# A9G_AHRS.net
KiCad netlist of a schematic drawn in Altium Designer
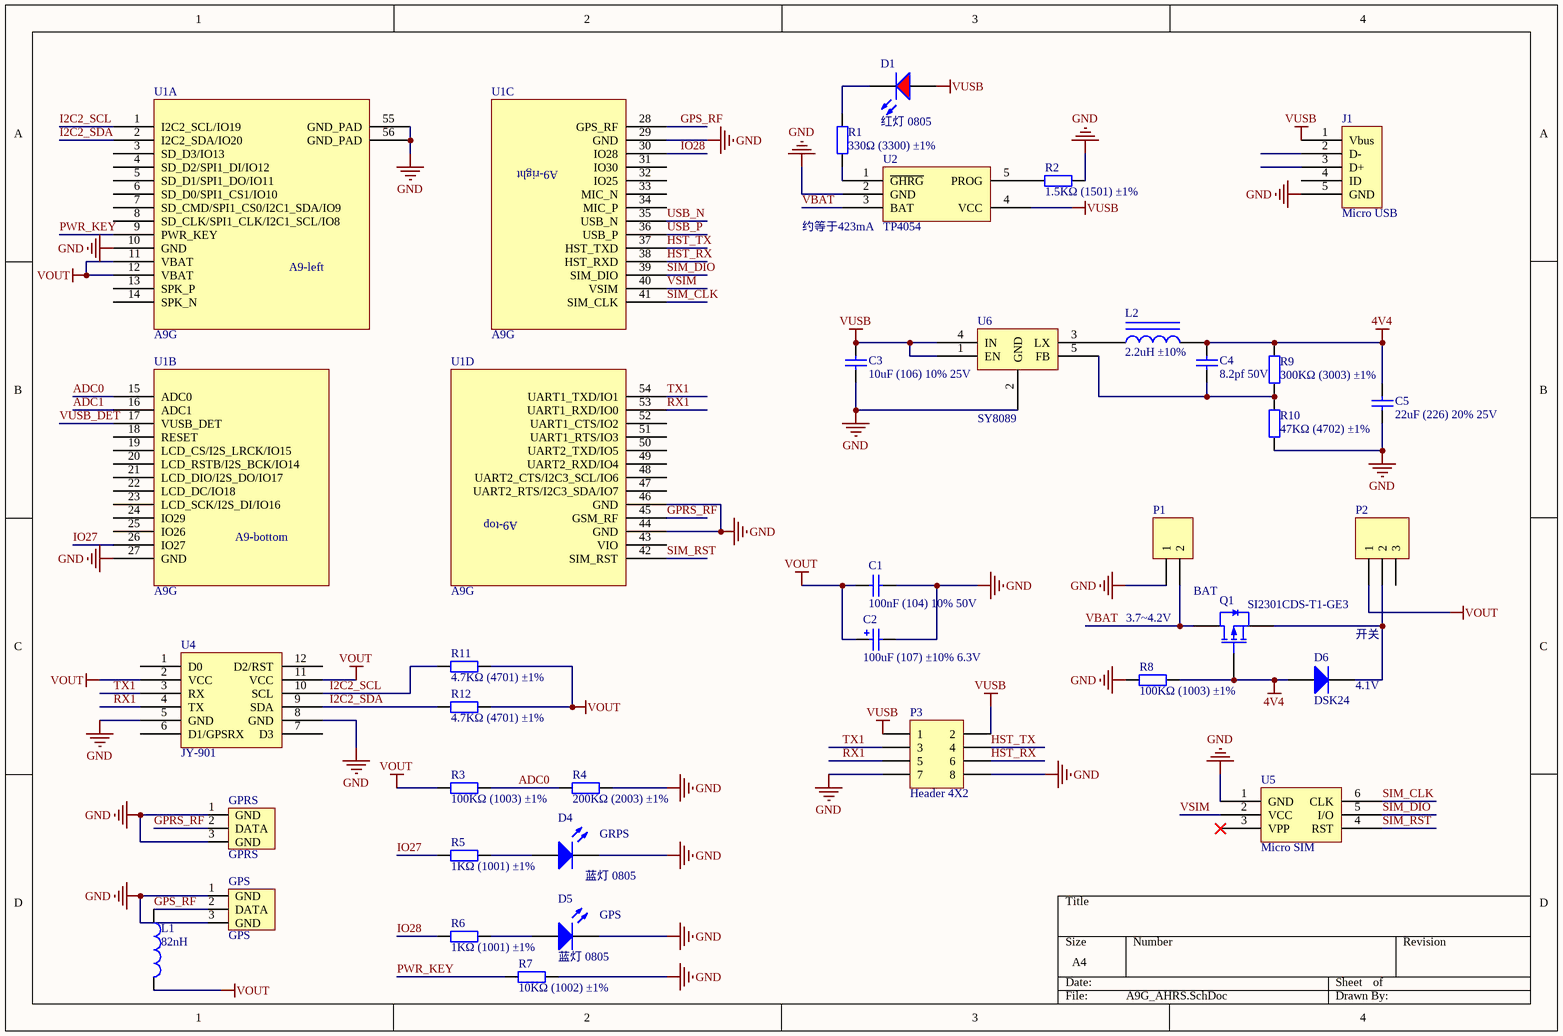
[diagram p0: A9G_AHRS.SchDoc]

(export (version "E")
  (design (tool "Eeschema 10.0.6"))
  (components
    (comp (ref "C1")
      (value "100nF (104) 10% 50V")
      (footprint "LC-0603_C")
      (description "贴片电容")
      (libsource (lib "Miscellaneous Devices LC") (part "0603 100nF (104) 10% 50V"))
    )
    (comp (ref "C2")
      (value "100uF (107) ±10% 6.3V")
      (footprint "LC-CASE-B_3528")
      (description "钽电容")
      (libsource (lib "Miscellaneous Devices LC") (part "3528 100uF (107) 10% 6.3V"))
    )
    (comp (ref "C3")
      (value "10uF (106) 10% 25V")
      (footprint "LC-0805_C")
      (description "贴片电容")
      (libsource (lib "Miscellaneous Devices LC") (part "0805 10uF (106) 10% 25V"))
    )
    (comp (ref "C4")
      (value "8.2pf 50V")
      (footprint "LC-0805_C")
      (description "贴片电容")
      (libsource (lib "Miscellaneous Devices LC") (part "0805 100nF(104) 10% 50V"))
    )
    (comp (ref "C5")
      (value "22uF (226) 20% 25V")
      (footprint "LC-0805_C")
      (description "贴片电容")
      (libsource (lib "Miscellaneous Devices LC") (part "0805 22uF (226) 20% 25V"))
    )
    (comp (ref "D1")
      (value "红灯 0805")
      (footprint "LC-0805_LED_S1")
      (description "发光二极管")
      (libsource (lib "Miscellaneous Devices LC") (part "0805 红灯"))
    )
    (comp (ref "D4")
      (value "蓝灯 0805")
      (footprint "LC-0805_LED_S1")
      (description "发光二极管")
      (libsource (lib "Miscellaneous Devices LC") (part "0805 蓝灯"))
    )
    (comp (ref "D5")
      (value "蓝灯 0805")
      (footprint "LC-0805_LED_S1")
      (description "发光二极管")
      (libsource (lib "Miscellaneous Devices LC") (part "0805 蓝灯"))
    )
    (comp (ref "D6")
      (value "DSK24")
      (footprint "LC-SOD-123")
      (description "肖特基二极管")
      (libsource (lib "Miscellaneous Devices LC") (part "SOD-123 B5819W  SL"))
    )
    (comp (ref "GPRS")
      (value "GPRS")
      (footprint "IPEX")
      (description "IPEX座")
      (libsource (lib "ATK_S1216F8_BD_V1.1") (part "IPEX"))
    )
    (comp (ref "GPS")
      (value "GPS")
      (footprint "IPEX")
      (description "IPEX座")
      (libsource (lib "ATK_S1216F8_BD_V1.1") (part "IPEX"))
    )
    (comp (ref "J1")
      (value "Micro USB")
      (footprint "Micro USB")
      (description "micro usb 母座")
      (libsource (lib "MyLib") (part "Micro USB"))
    )
    (comp (ref "L1")
      (value "82nH")
      (footprint "LC-0805_L")
      (description "Inductor")
      (fields (field (name "PUBLISHER") "Altium Limited"))
      (libsource (lib "Miscellaneous Devices") (part "Inductor"))
    )
    (comp (ref "L2")
      (value "2.2uH ±10%")
      (footprint "3015")
      (description "贴片电感")
      (libsource (lib "Miscellaneous Devices LC") (part "0805 2.2uH 10%"))
    )
    (comp (ref "P1")
      (value "BAT")
      (footprint "Motor_Header")
      (description "Header, 2-Pin")
      (fields (field (name "PUBLISHER") "Altium Limited"))
      (libsource (lib "Miscellaneous Connectors") (part "Header 2"))
    )
    (comp (ref "P2")
      (value "开关")
      (footprint "SW_6726")
      (description "Header, 3-Pin, Right Angle")
      (fields (field (name "PUBLISHER") "Altium Limited"))
      (libsource (lib "Miscellaneous Connectors") (part "Header 3H"))
    )
    (comp (ref "P3")
      (value "Header 4X2")
      (footprint "HDR2X4")
      (description "Header, 4-Pin, Dual row")
      (fields (field (name "PUBLISHER") "Altium Limited"))
      (libsource (lib "Miscellaneous Connectors") (part "Header 4X2"))
    )
    (comp (ref "Q1")
      (value "SI2301CDS-T1-GE3")
      (footprint "LC-SOT-23(SOT-23-3)")
      (description "MOS(场效应管)")
      (libsource (lib "Miscellaneous Devices LC") (part "SI2301CDS-T1-GE3"))
    )
    (comp (ref "R1")
      (value "330Ω (3300) ±1%")
      (footprint "LC-0805_R")
      (description "贴片电阻")
      (libsource (lib "Miscellaneous Devices LC") (part "0805 330Ω (3300) 1%"))
    )
    (comp (ref "R2")
      (value "1.5KΩ (1501) ±1%")
      (footprint "LC-0805_R")
      (description "贴片电阻")
      (libsource (lib "Miscellaneous Devices LC") (part "0805 1.5KΩ (1501) 1%"))
    )
    (comp (ref "R3")
      (value "100KΩ (1003) ±1%")
      (footprint "LC-0805_R")
      (description "贴片电阻")
      (libsource (lib "Miscellaneous Devices LC") (part "0805 100KΩ (1003) 1%"))
    )
    (comp (ref "R4")
      (value "200KΩ (2003) ±1%")
      (footprint "LC-0805_R")
      (description "贴片电阻")
      (libsource (lib "Miscellaneous Devices LC") (part "0805 200KΩ (2003) 1%"))
    )
    (comp (ref "R5")
      (value "1KΩ (1001) ±1%")
      (footprint "LC-0805_R")
      (description "贴片电阻")
      (libsource (lib "Miscellaneous Devices LC") (part "0805 1KΩ (1001) 1%"))
    )
    (comp (ref "R6")
      (value "1KΩ (1001) ±1%")
      (footprint "LC-0805_R")
      (description "贴片电阻")
      (libsource (lib "Miscellaneous Devices LC") (part "0805 1KΩ (1001) 1%"))
    )
    (comp (ref "R7")
      (value "10KΩ (1002) ±1%")
      (footprint "LC-0805_R")
      (description "贴片电阻")
      (libsource (lib "Miscellaneous Devices LC") (part "0805 10KΩ (1002) 1%"))
    )
    (comp (ref "R8")
      (value "100KΩ (1003) ±1%")
      (footprint "LC-0805_R")
      (description "贴片电阻")
      (libsource (lib "Miscellaneous Devices LC") (part "0805 100KΩ (1003) 1%"))
    )
    (comp (ref "R9")
      (value "300KΩ (3003) ±1%")
      (footprint "LC-0805_R")
      (description "贴片电阻")
      (libsource (lib "Miscellaneous Devices LC") (part "0805 300KΩ (3003) 1%"))
    )
    (comp (ref "R10")
      (value "47KΩ (4702) ±1%")
      (footprint "LC-0805_R")
      (description "贴片电阻")
      (libsource (lib "Miscellaneous Devices LC") (part "0805 47KΩ (4702) 1%"))
    )
    (comp (ref "R11")
      (value "4.7KΩ (4701) ±1%")
      (footprint "LC-0805_R")
      (description "贴片电阻")
      (libsource (lib "Miscellaneous Devices LC") (part "0805 4.7KΩ (4701) 1%"))
    )
    (comp (ref "R12")
      (value "4.7KΩ (4701) ±1%")
      (footprint "LC-0805_R")
      (description "贴片电阻")
      (libsource (lib "Miscellaneous Devices LC") (part "0805 4.7KΩ (4701) 1%"))
    )
    (comp (ref "U1") (value "A9G") (footprint "A9") (libsource (lib "") (part "A9_1")))
    (comp (ref "U2")
      (value "TP4054")
      (footprint "LC-SOT-23-5")
      (description "电池电源管理")
      (libsource (lib "Miscellaneous Devices LC") (part "TP4054"))
    )
    (comp (ref "U4")
      (value "JY-901")
      (footprint "JY-901")
      (description "君悦智控高精度9轴传感器")
      (libsource (lib "JYModule") (part "JY-901"))
    )
    (comp (ref "U5") (value "Micro SIM") (footprint "Micro SIM") (libsource (lib "MyLib") (part "Micro SIM")))
    (comp (ref "U6")
      (value "SY8089")
      (footprint "LC-SOT-23-5")
      (description "DC-DC regulator IC  capable of delivering up to 2A output current.")
      (libsource (lib "MyLib") (part "SY8089"))
    )
  )
  (nets
    (net (code "1") (name "/ADC0") (class "Default")
      (node (ref "R3") (pin "2") (pinfunction "2_2") (pintype "passive"))
      (node (ref "R4") (pin "1") (pinfunction "1_1") (pintype "passive"))
      (node (ref "U1") (pin "15") (pinfunction "ADC0_15") (pintype "passive"))
    )
    (net (code "2") (name "/ADC1") (class "Default")
      (node (ref "U1") (pin "16") (pinfunction "ADC1_16") (pintype "passive"))
    )
    (net (code "3") (name "/GPRS_RF") (class "Default")
      (node (ref "GPRS") (pin "2") (pinfunction "DATA_2") (pintype "passive"))
      (node (ref "U1") (pin "45") (pinfunction "GSM_RF_45") (pintype "passive"))
    )
    (net (code "4") (name "/GPS_RF") (class "Default")
      (node (ref "GPS") (pin "2") (pinfunction "DATA_2") (pintype "passive"))
      (node (ref "L1") (pin "1") (pinfunction "1_1") (pintype "passive"))
      (node (ref "U1") (pin "28") (pinfunction "GPS_RF_28") (pintype "passive"))
    )
    (net (code "5") (name "/HST_RX") (class "Default")
      (node (ref "P3") (pin "6") (pinfunction "6_6") (pintype "passive"))
      (node (ref "U1") (pin "38") (pinfunction "HST_RXD_38") (pintype "passive"))
    )
    (net (code "6") (name "/HST_TX") (class "Default")
      (node (ref "P3") (pin "4") (pinfunction "4_4") (pintype "passive"))
      (node (ref "U1") (pin "37") (pinfunction "HST_TXD_37") (pintype "passive"))
    )
    (net (code "7") (name "/I2C2_SCL") (class "Default")
      (node (ref "R11") (pin "1") (pinfunction "1_1") (pintype "passive"))
      (node (ref "U1") (pin "1") (pinfunction "I2C2_SCL/IO19_1") (pintype "passive"))
      (node (ref "U4") (pin "10") (pinfunction "SCL_10") (pintype "passive"))
    )
    (net (code "8") (name "/I2C2_SDA") (class "Default")
      (node (ref "R12") (pin "1") (pinfunction "1_1") (pintype "passive"))
      (node (ref "U1") (pin "2") (pinfunction "I2C2_SDA/IO20_2") (pintype "passive"))
      (node (ref "U4") (pin "9") (pinfunction "SDA_9") (pintype "passive"))
    )
    (net (code "9") (name "/IO27") (class "Default")
      (node (ref "R5") (pin "1") (pinfunction "1_1") (pintype "passive"))
      (node (ref "U1") (pin "26") (pinfunction "IO27_26") (pintype "passive"))
    )
    (net (code "10") (name "/IO28") (class "Default")
      (node (ref "R6") (pin "1") (pinfunction "1_1") (pintype "passive"))
      (node (ref "U1") (pin "30") (pinfunction "IO28_30") (pintype "passive"))
    )
    (net (code "11") (name "/PWR_KEY") (class "Default")
      (node (ref "R7") (pin "1") (pinfunction "1_1") (pintype "passive"))
      (node (ref "U1") (pin "9") (pinfunction "PWR_KEY_9") (pintype "passive"))
    )
    (net (code "12") (name "/RX1") (class "Default")
      (node (ref "P3") (pin "5") (pinfunction "5_5") (pintype "passive"))
      (node (ref "U1") (pin "53") (pinfunction "UART1_RXD/IO0_53") (pintype "passive"))
      (node (ref "U4") (pin "4") (pinfunction "TX_4") (pintype "passive"))
    )
    (net (code "13") (name "/SIM_CLK") (class "Default")
      (node (ref "U1") (pin "41") (pinfunction "SIM_CLK_41") (pintype "passive"))
      (node (ref "U5") (pin "6") (pinfunction "CLK_6") (pintype "passive"))
    )
    (net (code "14") (name "/SIM_DIO") (class "Default")
      (node (ref "U1") (pin "39") (pinfunction "SIM_DIO_39") (pintype "passive"))
      (node (ref "U5") (pin "5") (pinfunction "I/O_5") (pintype "passive"))
    )
    (net (code "15") (name "/SIM_RST") (class "Default")
      (node (ref "U1") (pin "42") (pinfunction "SIM_RST_42") (pintype "passive"))
      (node (ref "U5") (pin "4") (pinfunction "RST_4") (pintype "passive"))
    )
    (net (code "16") (name "/TX1") (class "Default")
      (node (ref "P3") (pin "3") (pinfunction "3_3") (pintype "passive"))
      (node (ref "U1") (pin "54") (pinfunction "UART1_TXD/IO1_54") (pintype "passive"))
      (node (ref "U4") (pin "3") (pinfunction "RX_3") (pintype "passive"))
    )
    (net (code "17") (name "/USB_N") (class "Default")
      (node (ref "U1") (pin "35") (pinfunction "USB_N_35") (pintype "passive"))
    )
    (net (code "18") (name "/USB_P") (class "Default")
      (node (ref "U1") (pin "36") (pinfunction "USB_P_36") (pintype "passive"))
    )
    (net (code "19") (name "/VBAT") (class "Default")
      (node (ref "P1") (pin "2") (pinfunction "2_2") (pintype "passive"))
      (node (ref "Q1") (pin "3") (pinfunction "D_3") (pintype "passive"))
      (node (ref "U2") (pin "3") (pinfunction "BAT_3") (pintype "passive"))
    )
    (net (code "20") (name "/VSIM") (class "Default")
      (node (ref "U1") (pin "40") (pinfunction "VSIM_40") (pintype "passive"))
      (node (ref "U5") (pin "2") (pinfunction "VCC_2") (pintype "passive"))
    )
    (net (code "21") (name "/VUSB_DET") (class "Default")
      (node (ref "U1") (pin "17") (pinfunction "VUSB_DET_17") (pintype "passive"))
    )
    (net (code "22") (name "4V4") (class "Default")
      (node (ref "C4") (pin "2") (pinfunction "2_2") (pintype "passive"))
      (node (ref "C5") (pin "2") (pinfunction "2_2") (pintype "passive"))
      (node (ref "D6") (pin "1") (pinfunction "A_1") (pintype "passive"))
      (node (ref "L2") (pin "2") (pinfunction "2_2") (pintype "passive"))
      (node (ref "Q1") (pin "1") (pinfunction "G_1") (pintype "passive"))
      (node (ref "R8") (pin "2") (pinfunction "2_2") (pintype "passive"))
      (node (ref "R9") (pin "2") (pinfunction "2_2") (pintype "passive"))
    )
    (net (code "23") (name "GND") (class "Default")
      (node (ref "C1") (pin "2") (pinfunction "2_2") (pintype "passive"))
      (node (ref "C2") (pin "2") (pinfunction "2_2") (pintype "passive"))
      (node (ref "C3") (pin "1") (pinfunction "1_1") (pintype "passive"))
      (node (ref "C5") (pin "1") (pinfunction "1_1") (pintype "passive"))
      (node (ref "D4") (pin "K") (pinfunction "K_K") (pintype "passive"))
      (node (ref "D5") (pin "K") (pinfunction "K_K") (pintype "passive"))
      (node (ref "GPRS") (pin "1") (pinfunction "GND_1") (pintype "passive"))
      (node (ref "GPRS") (pin "3") (pinfunction "GND_3") (pintype "passive"))
      (node (ref "GPS") (pin "1") (pinfunction "GND_1") (pintype "passive"))
      (node (ref "GPS") (pin "3") (pinfunction "GND_3") (pintype "passive"))
      (node (ref "J1") (pin "5") (pinfunction "GND_5") (pintype "passive"))
      (node (ref "P1") (pin "1") (pinfunction "1_1") (pintype "passive"))
      (node (ref "P3") (pin "7") (pinfunction "7_7") (pintype "passive"))
      (node (ref "P3") (pin "8") (pinfunction "8_8") (pintype "passive"))
      (node (ref "R10") (pin "1") (pinfunction "1_1") (pintype "passive"))
      (node (ref "R2") (pin "2") (pinfunction "2_2") (pintype "passive"))
      (node (ref "R4") (pin "2") (pinfunction "2_2") (pintype "passive"))
      (node (ref "R7") (pin "2") (pinfunction "2_2") (pintype "passive"))
      (node (ref "R8") (pin "1") (pinfunction "1_1") (pintype "passive"))
      (node (ref "U1") (pin "10") (pinfunction "GND_10") (pintype "passive"))
      (node (ref "U1") (pin "27") (pinfunction "GND_27") (pintype "passive"))
      (node (ref "U1") (pin "29") (pinfunction "GND_29") (pintype "passive"))
      (node (ref "U1") (pin "44") (pinfunction "GND_44") (pintype "passive"))
      (node (ref "U1") (pin "46") (pinfunction "GND_46") (pintype "passive"))
      (node (ref "U1") (pin "55") (pinfunction "GND_PAD_55") (pintype "passive"))
      (node (ref "U1") (pin "56") (pinfunction "GND_PAD_56") (pintype "passive"))
      (node (ref "U2") (pin "2") (pinfunction "GND_2") (pintype "passive"))
      (node (ref "U4") (pin "5") (pinfunction "GND_5") (pintype "passive"))
      (node (ref "U4") (pin "8") (pinfunction "GND_8") (pintype "passive"))
      (node (ref "U5") (pin "1") (pinfunction "GND_1") (pintype "passive"))
      (node (ref "U6") (pin "2") (pinfunction "GND_2") (pintype "passive"))
    )
    (net (code "24") (name "Net-(D1-PadK)") (class "Default")
      (node (ref "D1") (pin "K") (pinfunction "K_K") (pintype "passive"))
      (node (ref "R1") (pin "2") (pinfunction "2_2") (pintype "passive"))
    )
    (net (code "25") (name "Net-(D4-PadA)") (class "Default")
      (node (ref "D4") (pin "A") (pinfunction "A_A") (pintype "passive"))
      (node (ref "R5") (pin "2") (pinfunction "2_2") (pintype "passive"))
    )
    (net (code "26") (name "Net-(D5-PadA)") (class "Default")
      (node (ref "D5") (pin "A") (pinfunction "A_A") (pintype "passive"))
      (node (ref "R6") (pin "2") (pinfunction "2_2") (pintype "passive"))
    )
    (net (code "27") (name "Net-(D6-K)") (class "Default")
      (node (ref "D6") (pin "2") (pinfunction "K_2") (pintype "passive"))
      (node (ref "P2") (pin "2") (pinfunction "2_2") (pintype "passive"))
      (node (ref "Q1") (pin "2") (pinfunction "S_2") (pintype "passive"))
    )
    (net (code "28") (name "Net-(U2-PROG)") (class "Default")
      (node (ref "R2") (pin "1") (pinfunction "1_1") (pintype "passive"))
      (node (ref "U2") (pin "5") (pinfunction "PROG_5") (pintype "passive"))
    )
    (net (code "29") (name "Net-(U2-~{GHRG})") (class "Default")
      (node (ref "R1") (pin "1") (pinfunction "1_1") (pintype "passive"))
      (node (ref "U2") (pin "1") (pinfunction "~{GHRG}_1") (pintype "passive"))
    )
    (net (code "30") (name "Net-(U6-FB)") (class "Default")
      (node (ref "C4") (pin "1") (pinfunction "1_1") (pintype "passive"))
      (node (ref "R10") (pin "2") (pinfunction "2_2") (pintype "passive"))
      (node (ref "R9") (pin "1") (pinfunction "1_1") (pintype "passive"))
      (node (ref "U6") (pin "5") (pinfunction "FB_5") (pintype "passive"))
    )
    (net (code "31") (name "Net-(U6-LX)") (class "Default")
      (node (ref "L2") (pin "1") (pinfunction "1_1") (pintype "passive"))
      (node (ref "U6") (pin "3") (pinfunction "LX_3") (pintype "passive"))
    )
    (net (code "32") (name "VOUT") (class "Default")
      (node (ref "C1") (pin "1") (pinfunction "1_1") (pintype "passive"))
      (node (ref "C2") (pin "1") (pinfunction "1_1") (pintype "passive"))
      (node (ref "L1") (pin "2") (pinfunction "2_2") (pintype "passive"))
      (node (ref "P2") (pin "1") (pinfunction "1_1") (pintype "passive"))
      (node (ref "R11") (pin "2") (pinfunction "2_2") (pintype "passive"))
      (node (ref "R12") (pin "2") (pinfunction "2_2") (pintype "passive"))
      (node (ref "R3") (pin "1") (pinfunction "1_1") (pintype "passive"))
      (node (ref "U1") (pin "11") (pinfunction "VBAT_11") (pintype "passive"))
      (node (ref "U1") (pin "12") (pinfunction "VBAT_12") (pintype "passive"))
      (node (ref "U4") (pin "11") (pinfunction "VCC_11") (pintype "passive"))
      (node (ref "U4") (pin "2") (pinfunction "VCC_2") (pintype "passive"))
    )
    (net (code "33") (name "VUSB") (class "Default")
      (node (ref "C3") (pin "2") (pinfunction "2_2") (pintype "passive"))
      (node (ref "D1") (pin "A") (pinfunction "A_A") (pintype "passive"))
      (node (ref "J1") (pin "1") (pinfunction "Vbus_1") (pintype "passive"))
      (node (ref "P3") (pin "1") (pinfunction "1_1") (pintype "passive"))
      (node (ref "P3") (pin "2") (pinfunction "2_2") (pintype "passive"))
      (node (ref "U2") (pin "4") (pinfunction "VCC_4") (pintype "passive"))
      (node (ref "U6") (pin "1") (pinfunction "EN_1") (pintype "passive"))
      (node (ref "U6") (pin "4") (pinfunction "IN_4") (pintype "passive"))
    )
    (net (code "34") (name "unconnected-(J1-D+-Pad3)") (class "Default")
      (node (ref "J1") (pin "3") (pinfunction "D+_3") (pintype "passive"))
    )
    (net (code "35") (name "unconnected-(J1-D--Pad2)") (class "Default")
      (node (ref "J1") (pin "2") (pinfunction "D-_2") (pintype "passive"))
    )
    (net (code "36") (name "unconnected-(J1-ID-Pad4)") (class "Default")
      (node (ref "J1") (pin "4") (pinfunction "ID_4") (pintype "passive"))
    )
    (net (code "37") (name "unconnected-(P2-Pad3)") (class "Default")
      (node (ref "P2") (pin "3") (pinfunction "3_3") (pintype "passive"))
    )
    (net (code "38") (name "unconnected-(U1A-SD_CLK{slash}SPI1_CLK{slash}I2C1_SCL{slash}IO8-Pad8)") (class "Default")
      (node (ref "U1") (pin "8") (pinfunction "SD_CLK/SPI1_CLK/I2C1_SCL/IO8_8") (pintype "passive"))
    )
    (net (code "39") (name "unconnected-(U1A-SD_CMD{slash}SPI1_CS0{slash}I2C1_SDA{slash}IO9-Pad7)") (class "Default")
      (node (ref "U1") (pin "7") (pinfunction "SD_CMD/SPI1_CS0/I2C1_SDA/IO9_7") (pintype "passive"))
    )
    (net (code "40") (name "unconnected-(U1A-SD_D0{slash}SPI1_CS1{slash}IO10-Pad6)") (class "Default")
      (node (ref "U1") (pin "6") (pinfunction "SD_D0/SPI1_CS1/IO10_6") (pintype "passive"))
    )
    (net (code "41") (name "unconnected-(U1A-SD_D1{slash}SPI1_DO{slash}IO11-Pad5)") (class "Default")
      (node (ref "U1") (pin "5") (pinfunction "SD_D1/SPI1_DO/IO11_5") (pintype "passive"))
    )
    (net (code "42") (name "unconnected-(U1A-SD_D2{slash}SPI1_DI{slash}IO12-Pad4)") (class "Default")
      (node (ref "U1") (pin "4") (pinfunction "SD_D2/SPI1_DI/IO12_4") (pintype "passive"))
    )
    (net (code "43") (name "unconnected-(U1A-SD_D3{slash}IO13-Pad3)") (class "Default")
      (node (ref "U1") (pin "3") (pinfunction "SD_D3/IO13_3") (pintype "passive"))
    )
    (net (code "44") (name "unconnected-(U1A-SPK_N-Pad14)") (class "Default")
      (node (ref "U1") (pin "14") (pinfunction "SPK_N_14") (pintype "passive"))
    )
    (net (code "45") (name "unconnected-(U1A-SPK_P-Pad13)") (class "Default")
      (node (ref "U1") (pin "13") (pinfunction "SPK_P_13") (pintype "passive"))
    )
    (net (code "46") (name "unconnected-(U1B-IO26-Pad25)") (class "Default")
      (node (ref "U1") (pin "25") (pinfunction "IO26_25") (pintype "passive"))
    )
    (net (code "47") (name "unconnected-(U1B-IO29-Pad24)") (class "Default")
      (node (ref "U1") (pin "24") (pinfunction "IO29_24") (pintype "passive"))
    )
    (net (code "48") (name "unconnected-(U1B-LCD_CS{slash}I2S_LRCK{slash}IO15-Pad19)") (class "Default")
      (node (ref "U1") (pin "19") (pinfunction "LCD_CS/I2S_LRCK/IO15_19") (pintype "passive"))
    )
    (net (code "49") (name "unconnected-(U1B-LCD_DC{slash}IO18-Pad22)") (class "Default")
      (node (ref "U1") (pin "22") (pinfunction "LCD_DC/IO18_22") (pintype "passive"))
    )
    (net (code "50") (name "unconnected-(U1B-LCD_DIO{slash}I2S_DO{slash}IO17-Pad21)") (class "Default")
      (node (ref "U1") (pin "21") (pinfunction "LCD_DIO/I2S_DO/IO17_21") (pintype "passive"))
    )
    (net (code "51") (name "unconnected-(U1B-LCD_RSTB{slash}I2S_BCK{slash}IO14-Pad20)") (class "Default")
      (node (ref "U1") (pin "20") (pinfunction "LCD_RSTB/I2S_BCK/IO14_20") (pintype "passive"))
    )
    (net (code "52") (name "unconnected-(U1B-LCD_SCK{slash}I2S_DI{slash}IO16-Pad23)") (class "Default")
      (node (ref "U1") (pin "23") (pinfunction "LCD_SCK/I2S_DI/IO16_23") (pintype "passive"))
    )
    (net (code "53") (name "unconnected-(U1B-RESET-Pad18)") (class "Default")
      (node (ref "U1") (pin "18") (pinfunction "RESET_18") (pintype "passive"))
    )
    (net (code "54") (name "unconnected-(U1C-IO25-Pad32)") (class "Default")
      (node (ref "U1") (pin "32") (pinfunction "IO25_32") (pintype "passive"))
    )
    (net (code "55") (name "unconnected-(U1C-IO30-Pad31)") (class "Default")
      (node (ref "U1") (pin "31") (pinfunction "IO30_31") (pintype "passive"))
    )
    (net (code "56") (name "unconnected-(U1C-MIC_N-Pad33)") (class "Default")
      (node (ref "U1") (pin "33") (pinfunction "MIC_N_33") (pintype "passive"))
    )
    (net (code "57") (name "unconnected-(U1C-MIC_P-Pad34)") (class "Default")
      (node (ref "U1") (pin "34") (pinfunction "MIC_P_34") (pintype "passive"))
    )
    (net (code "58") (name "unconnected-(U1D-UART1_CTS{slash}IO2-Pad52)") (class "Default")
      (node (ref "U1") (pin "52") (pinfunction "UART1_CTS/IO2_52") (pintype "passive"))
    )
    (net (code "59") (name "unconnected-(U1D-UART1_RTS{slash}IO3-Pad51)") (class "Default")
      (node (ref "U1") (pin "51") (pinfunction "UART1_RTS/IO3_51") (pintype "passive"))
    )
    (net (code "60") (name "unconnected-(U1D-UART2_CTS{slash}I2C3_SCL{slash}IO6-Pad48)") (class "Default")
      (node (ref "U1") (pin "48") (pinfunction "UART2_CTS/I2C3_SCL/IO6_48") (pintype "passive"))
    )
    (net (code "61") (name "unconnected-(U1D-UART2_RTS{slash}I2C3_SDA{slash}IO7-Pad47)") (class "Default")
      (node (ref "U1") (pin "47") (pinfunction "UART2_RTS/I2C3_SDA/IO7_47") (pintype "passive"))
    )
    (net (code "62") (name "unconnected-(U1D-UART2_RXD{slash}IO4-Pad49)") (class "Default")
      (node (ref "U1") (pin "49") (pinfunction "UART2_RXD/IO4_49") (pintype "passive"))
    )
    (net (code "63") (name "unconnected-(U1D-UART2_TXD{slash}IO5-Pad50)") (class "Default")
      (node (ref "U1") (pin "50") (pinfunction "UART2_TXD/IO5_50") (pintype "passive"))
    )
    (net (code "64") (name "unconnected-(U1D-VIO-Pad43)") (class "Default")
      (node (ref "U1") (pin "43") (pinfunction "VIO_43") (pintype "passive"))
    )
    (net (code "65") (name "unconnected-(U4-D0-Pad1)") (class "Default")
      (node (ref "U4") (pin "1") (pinfunction "D0_1") (pintype "passive"))
    )
    (net (code "66") (name "unconnected-(U4-D1{slash}GPSRX-Pad6)") (class "Default")
      (node (ref "U4") (pin "6") (pinfunction "D1/GPSRX_6") (pintype "passive"))
    )
    (net (code "67") (name "unconnected-(U4-D2{slash}RST-Pad12)") (class "Default")
      (node (ref "U4") (pin "12") (pinfunction "D2/RST_12") (pintype "passive"))
    )
    (net (code "68") (name "unconnected-(U4-D3-Pad7)") (class "Default")
      (node (ref "U4") (pin "7") (pinfunction "D3_7") (pintype "passive"))
    )
    (net (code "69") (name "unconnected-(U5-VPP-Pad3)") (class "Default")
      (node (ref "U5") (pin "3") (pinfunction "VPP_3") (pintype "passive+no_connect"))
    )
  )
)
